# fp_js110.net
KiCad netlist of a schematic drawn in EAGLE
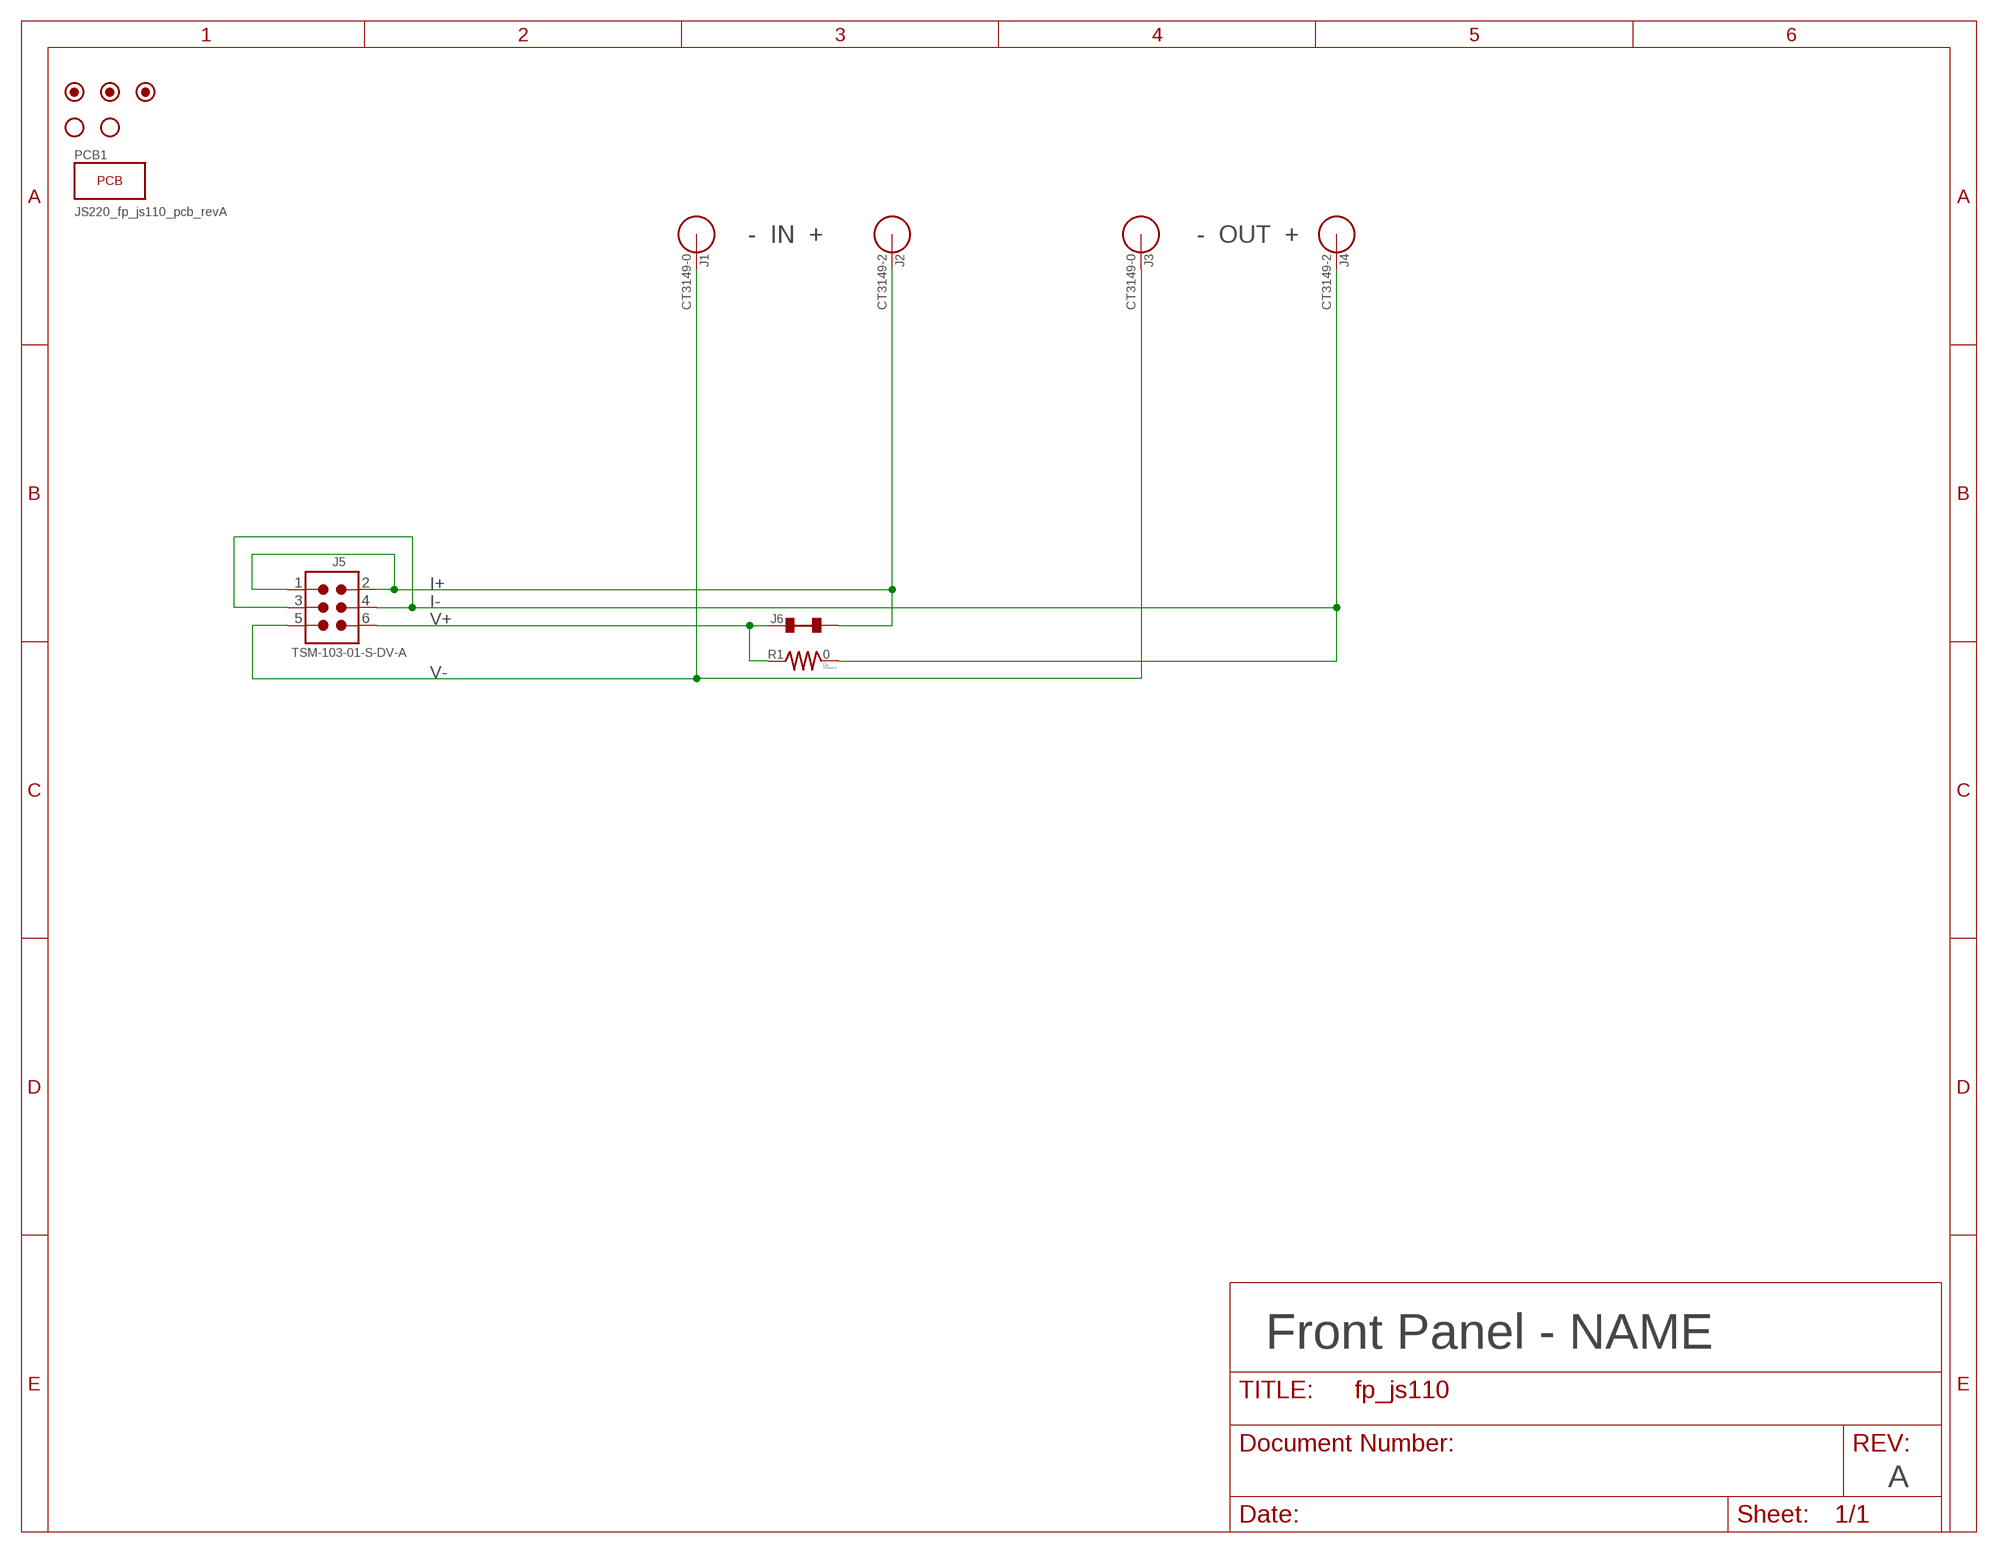
[diagram p0: schematic, sheet 1]

(export (version "E")
  (design (tool "Eeschema 10.0.6"))
  (components
    (comp (ref "FUD1")
      (value "FIDUCIAL_1MM")
      (footprint "eagle-import:FIDUCIAL_1MM_2MM")
      (libsource (lib "eagle-import") (part "FIDUCIAL_1MM"))
    )
    (comp (ref "FUD2")
      (value "FIDUCIAL_1MM")
      (footprint "eagle-import:FIDUCIAL_1MM_2MM")
      (libsource (lib "eagle-import") (part "FIDUCIAL_1MM"))
    )
    (comp (ref "FUD3")
      (value "FIDUCIAL_1MM")
      (footprint "eagle-import:FIDUCIAL_1MM_2MM")
      (libsource (lib "eagle-import") (part "FIDUCIAL_1MM"))
    )
    (comp (ref "H1")
      (value "HOLE_#6_NORESTRICT")
      (footprint "eagle-import:HOLE_3.5MM_NORESTRICT")
      (libsource (lib "eagle-import") (part "HOLE_#6_NORESTRICT"))
    )
    (comp (ref "H2")
      (value "HOLE_#6_NORESTRICT")
      (footprint "eagle-import:HOLE_3.5MM_NORESTRICT")
      (libsource (lib "eagle-import") (part "HOLE_#6_NORESTRICT"))
    )
    (comp (ref "J1")
      (value "CT3149-0")
      (footprint "eagle-import:CT3149")
      (libsource (lib "eagle-import") (part "BANANA-JACK_CT3149"))
    )
    (comp (ref "J2")
      (value "CT3149-2")
      (footprint "eagle-import:CT3149")
      (libsource (lib "eagle-import") (part "BANANA-JACK_CT3149"))
    )
    (comp (ref "J3")
      (value "CT3149-0")
      (footprint "eagle-import:CT3149")
      (libsource (lib "eagle-import") (part "BANANA-JACK_CT3149"))
    )
    (comp (ref "J4")
      (value "CT3149-2")
      (footprint "eagle-import:CT3149")
      (libsource (lib "eagle-import") (part "BANANA-JACK_CT3149"))
    )
    (comp (ref "J5")
      (value "TSM-103-01-S-DV-A")
      (footprint "eagle-import:CONN_0.1_3X2_MSA")
      (libsource (lib "eagle-import") (part "CONN_0.1_3X2_MSA"))
    )
    (comp (ref "J6")
      (value "TRACE_CUT0603")
      (footprint "eagle-import:J0603")
      (libsource (lib "eagle-import") (part "TRACE_CUT0603"))
    )
    (comp (ref "R1")
      (value "0")
      (footprint "eagle-import:0603")
      (fields
        (field (name "TOLERANCE") "1%")
        (field (name "WATTAGE") "0.1W")
        (field (name "TEMP_CO") "100 ppm/°C")
      )
      (libsource (lib "eagle-import") (part "RESISTOR_0603"))
    )
  )
  (nets
    (net (code "1") (name "/I+") (class "Default")
      (node (ref "J2") (pin "A") (pinfunction "1_A") (pintype "bidirectional"))
      (node (ref "J5") (pin "1") (pinfunction "1_1") (pintype "bidirectional"))
      (node (ref "J5") (pin "2") (pinfunction "2_2") (pintype "bidirectional"))
      (node (ref "J6") (pin "2") (pinfunction "P$2_2") (pintype "bidirectional"))
    )
    (net (code "2") (name "/I-") (class "Default")
      (node (ref "J4") (pin "A") (pinfunction "1_A") (pintype "bidirectional"))
      (node (ref "J5") (pin "3") (pinfunction "3_3") (pintype "bidirectional"))
      (node (ref "J5") (pin "4") (pinfunction "4_4") (pintype "bidirectional"))
      (node (ref "R1") (pin "2") (pinfunction "P$2_2") (pintype "bidirectional"))
    )
    (net (code "3") (name "/V+") (class "Default")
      (node (ref "J5") (pin "6") (pinfunction "6_6") (pintype "bidirectional"))
      (node (ref "J6") (pin "1") (pinfunction "P$1_1") (pintype "bidirectional"))
      (node (ref "R1") (pin "1") (pinfunction "P$1_1") (pintype "bidirectional"))
    )
    (net (code "4") (name "/V-") (class "Default")
      (node (ref "J1") (pin "A") (pinfunction "1_A") (pintype "bidirectional"))
      (node (ref "J3") (pin "A") (pinfunction "1_A") (pintype "bidirectional"))
      (node (ref "J5") (pin "5") (pinfunction "5_5") (pintype "bidirectional"))
    )
  )
)
